# 12-RTL8111H-3.net
KiCad netlist of a schematic drawn in Altium Designer
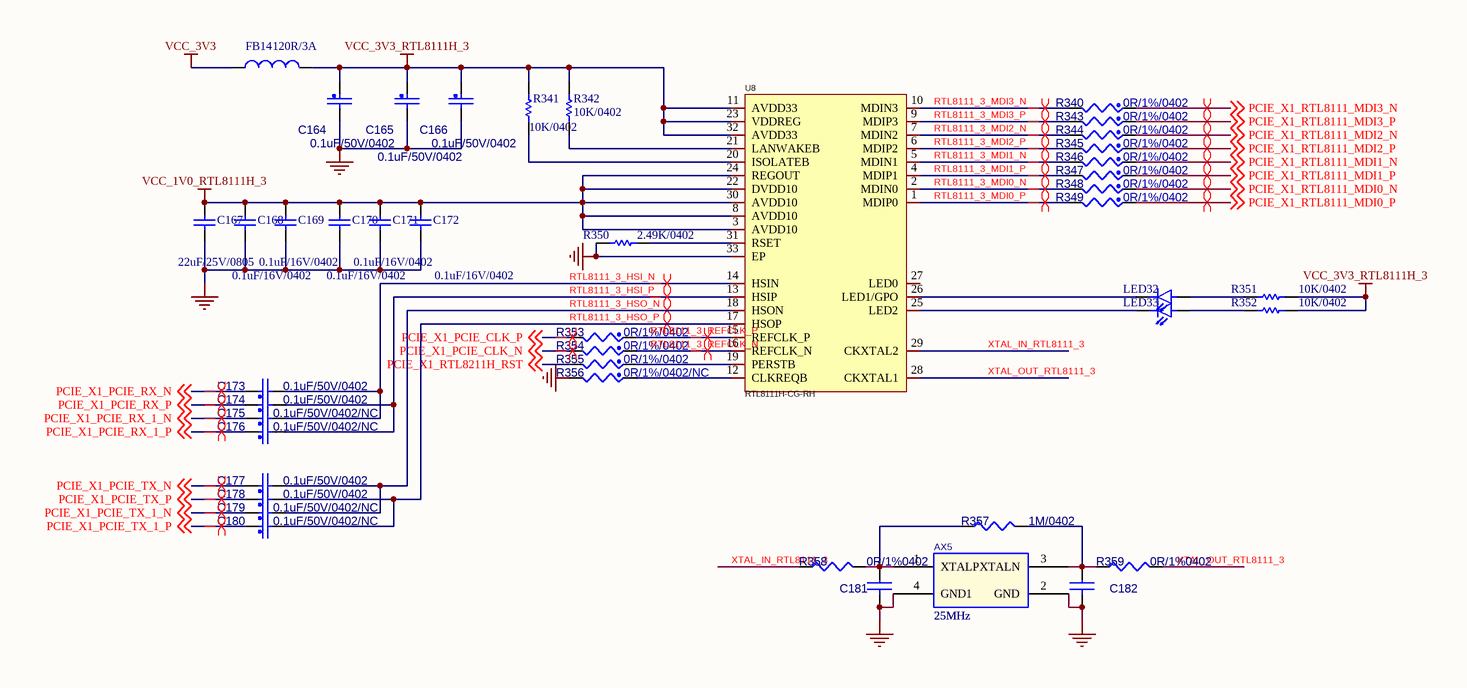
[diagram p0: 12-RTL8111H-3.schdoc]

(export (version "E")
  (design (tool "Eeschema 10.0.6"))
  (components
    (comp (ref "AX5")
      (value "25MHz")
      (footprint "2016")
      (fields (field (name "ALTIUM_VALUE") "25MHz"))
      (libsource (lib "*") (part "XTAL_0"))
    )
    (comp (ref "C164")
      (value "0.1uF/50V/0402")
      (footprint "C0402")
      (description "GCM155R71H104KE02/MURATA")
      (fields (field (name "TOLERANCE") "10%") (field (name "VOLTAGE") "16V"))
      (libsource (lib "*") (part "CAP_NP"))
    )
    (comp (ref "C165")
      (value "0.1uF/50V/0402")
      (footprint "C0402")
      (description "GCM155R71H104KE02/MURATA")
      (fields (field (name "TOLERANCE") "10%") (field (name "VOLTAGE") "16V"))
      (libsource (lib "*") (part "CAP_NP"))
    )
    (comp (ref "C166")
      (value "0.1uF/50V/0402")
      (footprint "C0402")
      (description "GCM155R71H104KE02/MURATA")
      (fields (field (name "TOLERANCE") "10%") (field (name "VOLTAGE") "16V"))
      (libsource (lib "*") (part "CAP_NP"))
    )
    (comp (ref "C167")
      (value "22uF/25V/0805")
      (description "Capacitor")
      (fields (field (name "PUBLISHER") "Altium Limited"))
      (libsource (lib "LIBS") (part "CAP"))
    )
    (comp (ref "C168")
      (value "0.1uF/16V/0402")
      (description "Capacitor")
      (fields (field (name "PUBLISHER") "Altium Limited"))
      (libsource (lib "LIBS") (part "CAP"))
    )
    (comp (ref "C169")
      (value "0.1uF/16V/0402")
      (description "Capacitor")
      (fields (field (name "PUBLISHER") "Altium Limited"))
      (libsource (lib "LIBS") (part "CAP"))
    )
    (comp (ref "C170")
      (value "0.1uF/16V/0402")
      (description "Capacitor")
      (fields (field (name "PUBLISHER") "Altium Limited"))
      (libsource (lib "LIBS") (part "CAP"))
    )
    (comp (ref "C171")
      (value "0.1uF/16V/0402")
      (description "Capacitor")
      (fields (field (name "PUBLISHER") "Altium Limited"))
      (libsource (lib "LIBS") (part "CAP"))
    )
    (comp (ref "C172")
      (value "0.1uF/16V/0402")
      (description "Capacitor")
      (fields (field (name "PUBLISHER") "Altium Limited"))
      (libsource (lib "LIBS") (part "CAP"))
    )
    (comp (ref "C173")
      (value "0.1uF/50V/0402")
      (footprint "C0402")
      (description "GCM155R71H104KE02/MURATA")
      (fields (field (name "TOLERANCE") "10%") (field (name "VOLTAGE") "16V"))
      (libsource (lib "*") (part "CAP_NP"))
    )
    (comp (ref "C174")
      (value "0.1uF/50V/0402")
      (footprint "C0402")
      (description "GCM155R71H104KE02/MURATA")
      (fields (field (name "TOLERANCE") "10%") (field (name "VOLTAGE") "16V"))
      (libsource (lib "*") (part "CAP_NP"))
    )
    (comp (ref "C175")
      (value "0.1uF/50V/0402/NC")
      (footprint "C0402")
      (description "GCM155R71H104KE02/MURATA")
      (fields (field (name "TOLERANCE") "10%") (field (name "VOLTAGE") "16V"))
      (libsource (lib "*") (part "CAP_NP"))
    )
    (comp (ref "C176")
      (value "0.1uF/50V/0402/NC")
      (footprint "C0402")
      (description "GCM155R71H104KE02/MURATA")
      (fields (field (name "TOLERANCE") "10%") (field (name "VOLTAGE") "16V"))
      (libsource (lib "*") (part "CAP_NP"))
    )
    (comp (ref "C177")
      (value "0.1uF/50V/0402")
      (footprint "C0402")
      (description "GCM155R71H104KE02/MURATA")
      (fields (field (name "TOLERANCE") "10%") (field (name "VOLTAGE") "16V"))
      (libsource (lib "*") (part "CAP_NP"))
    )
    (comp (ref "C178")
      (value "0.1uF/50V/0402")
      (footprint "C0402")
      (description "GCM155R71H104KE02/MURATA")
      (fields (field (name "TOLERANCE") "10%") (field (name "VOLTAGE") "16V"))
      (libsource (lib "*") (part "CAP_NP"))
    )
    (comp (ref "C179")
      (value "0.1uF/50V/0402/NC")
      (footprint "C0402")
      (description "GCM155R71H104KE02/MURATA")
      (fields (field (name "TOLERANCE") "10%") (field (name "VOLTAGE") "16V"))
      (libsource (lib "*") (part "CAP_NP"))
    )
    (comp (ref "C180")
      (value "0.1uF/50V/0402/NC")
      (footprint "C0402")
      (description "GCM155R71H104KE02/MURATA")
      (fields (field (name "TOLERANCE") "10%") (field (name "VOLTAGE") "16V"))
      (libsource (lib "*") (part "CAP_NP"))
    )
    (comp (ref "C181") (value "CAP NP_Dup3") (footprint "C0402") (libsource (lib "*") (part "CAP NP_Dup3")))
    (comp (ref "C182") (value "CAP NP_Dup3") (footprint "C0402") (libsource (lib "*") (part "CAP NP_Dup3")))
    (comp (ref "FB14")
      (value "120R/3A")
      (footprint "L0603")
      (description "BLM18KG121TN1D")
      (fields (field (name "PUBLISHER") "Altium Limited"))
      (libsource (lib "LIBS") (part "Inductor"))
    )
    (comp (ref "LED32") (value "LED_GREEN") (footprint "LED0603") (libsource (lib "LIBS") (part "LED")))
    (comp (ref "LED33") (value "LED_GREEN") (footprint "LED0603") (libsource (lib "LIBS") (part "LED")))
    (comp (ref "R340")
      (value "0R/1%/0402")
      (footprint "R0402")
      (description "AC0402FR-070RL/YAGEO")
      (fields (field (name "TOLERANCE") "1%") (field (name "Comment") "RES_Dup2"))
      (libsource (lib "*") (part "RES_Dup2"))
    )
    (comp (ref "R341")
      (value "10K/0402")
      (footprint "R0402")
      (description "Semiconductor Resistor")
      (fields (field (name "PUBLISHER") "Altium Limited"))
      (libsource (lib "LIBS") (part "Res Semi"))
    )
    (comp (ref "R342")
      (value "10K/0402")
      (footprint "R0402")
      (description "Semiconductor Resistor")
      (fields (field (name "PUBLISHER") "Altium Limited"))
      (libsource (lib "LIBS") (part "Res Semi"))
    )
    (comp (ref "R343")
      (value "0R/1%/0402")
      (footprint "R0402")
      (description "AC0402FR-070RL/YAGEO")
      (fields (field (name "TOLERANCE") "1%") (field (name "Comment") "RES_Dup2"))
      (libsource (lib "*") (part "RES_Dup2"))
    )
    (comp (ref "R344")
      (value "0R/1%/0402")
      (footprint "R0402")
      (description "AC0402FR-070RL/YAGEO")
      (fields (field (name "TOLERANCE") "1%") (field (name "Comment") "RES_Dup2"))
      (libsource (lib "*") (part "RES_Dup2"))
    )
    (comp (ref "R345")
      (value "0R/1%/0402")
      (footprint "R0402")
      (description "AC0402FR-070RL/YAGEO")
      (fields (field (name "TOLERANCE") "1%") (field (name "Comment") "RES_Dup2"))
      (libsource (lib "*") (part "RES_Dup2"))
    )
    (comp (ref "R346")
      (value "0R/1%/0402")
      (footprint "R0402")
      (description "AC0402FR-070RL/YAGEO")
      (fields (field (name "TOLERANCE") "1%") (field (name "Comment") "RES_Dup2"))
      (libsource (lib "*") (part "RES_Dup2"))
    )
    (comp (ref "R347")
      (value "0R/1%/0402")
      (footprint "R0402")
      (description "AC0402FR-070RL/YAGEO")
      (fields (field (name "TOLERANCE") "1%") (field (name "Comment") "RES_Dup2"))
      (libsource (lib "*") (part "RES_Dup2"))
    )
    (comp (ref "R348")
      (value "0R/1%/0402")
      (footprint "R0402")
      (description "AC0402FR-070RL/YAGEO")
      (fields (field (name "TOLERANCE") "1%") (field (name "Comment") "RES_Dup2"))
      (libsource (lib "*") (part "RES_Dup2"))
    )
    (comp (ref "R349")
      (value "0R/1%/0402")
      (footprint "R0402")
      (description "AC0402FR-070RL/YAGEO")
      (fields (field (name "TOLERANCE") "1%") (field (name "Comment") "RES_Dup2"))
      (libsource (lib "*") (part "RES_Dup2"))
    )
    (comp (ref "R350")
      (value "2.49K/0402")
      (footprint "R0402")
      (description "Semiconductor Resistor")
      (fields (field (name "PUBLISHER") "Altium Limited"))
      (libsource (lib "LIBS") (part "Res Semi"))
    )
    (comp (ref "R351")
      (value "10K/0402")
      (footprint "R0402")
      (description "Semiconductor Resistor")
      (fields (field (name "PUBLISHER") "Altium Limited"))
      (libsource (lib "LIBS") (part "Res Semi"))
    )
    (comp (ref "R352")
      (value "10K/0402")
      (footprint "R0402")
      (description "Semiconductor Resistor")
      (fields (field (name "PUBLISHER") "Altium Limited"))
      (libsource (lib "LIBS") (part "Res Semi"))
    )
    (comp (ref "R353")
      (value "0R/1%/0402")
      (footprint "R0402")
      (description "AC0402FR-070RL/YAGEO")
      (fields (field (name "TOLERANCE") "1%") (field (name "Comment") "RES_Dup2"))
      (libsource (lib "*") (part "RES_Dup2"))
    )
    (comp (ref "R354")
      (value "0R/1%/0402")
      (footprint "R0402")
      (description "AC0402FR-070RL/YAGEO")
      (fields (field (name "TOLERANCE") "1%") (field (name "Comment") "RES_Dup2"))
      (libsource (lib "*") (part "RES_Dup2"))
    )
    (comp (ref "R355")
      (value "0R/1%/0402")
      (footprint "R0402")
      (description "AC0402FR-070RL/YAGEO")
      (fields (field (name "TOLERANCE") "1%") (field (name "Comment") "RES_Dup2"))
      (libsource (lib "*") (part "RES_Dup2"))
    )
    (comp (ref "R356")
      (value "0R/1%/0402/NC")
      (footprint "R0402")
      (description "AC0402FR-070RL/YAGEO")
      (fields (field (name "TOLERANCE") "1%") (field (name "Comment") "RES_Dup2"))
      (libsource (lib "*") (part "RES_Dup2"))
    )
    (comp (ref "R357")
      (value "1M/0402")
      (footprint "R0402")
      (fields (field (name "Comment") "R_Dup3"))
      (libsource (lib "*") (part "R_Dup3"))
    )
    (comp (ref "R358")
      (value "0R/1%0402")
      (footprint "R0402")
      (fields (field (name "Comment") "R_Dup3"))
      (libsource (lib "*") (part "R_Dup3"))
    )
    (comp (ref "R359")
      (value "0R/1%0402")
      (footprint "R0402")
      (fields (field (name "Comment") "R_Dup3"))
      (libsource (lib "*") (part "R_Dup3"))
    )
    (comp (ref "U8")
      (value "RTL8111H-CG-RH")
      (footprint "RTL8111H-CG-RH")
      (fields (field (name "MANUFACTURER") "REALTEK(瑞昱)") (field (name "MANUFACTURER PART") "RTL8111H-CG"))
      (libsource (lib "17267508141_1726750814") (part "RTL8111H-CG"))
    )
  )
  (nets
    (net (code "1") (name "/RTL8111_3_HSI_N") (class "Default")
      (node (ref "C173") (pin "2") (pinfunction "2_2") (pintype "passive"))
      (node (ref "C175") (pin "2") (pinfunction "2_2") (pintype "passive"))
      (node (ref "U8") (pin "14") (pinfunction "HSIN_14") (pintype "passive"))
    )
    (net (code "2") (name "/RTL8111_3_HSI_P") (class "Default")
      (node (ref "C174") (pin "2") (pinfunction "2_2") (pintype "passive"))
      (node (ref "C176") (pin "2") (pinfunction "2_2") (pintype "passive"))
      (node (ref "U8") (pin "13") (pinfunction "HSIP_13") (pintype "passive"))
    )
    (net (code "3") (name "/RTL8111_3_HSO_N") (class "Default")
      (node (ref "C177") (pin "2") (pinfunction "2_2") (pintype "passive"))
      (node (ref "C179") (pin "2") (pinfunction "2_2") (pintype "passive"))
      (node (ref "U8") (pin "18") (pinfunction "HSON_18") (pintype "passive"))
    )
    (net (code "4") (name "/RTL8111_3_HSO_P") (class "Default")
      (node (ref "C178") (pin "2") (pinfunction "2_2") (pintype "passive"))
      (node (ref "C180") (pin "2") (pinfunction "2_2") (pintype "passive"))
      (node (ref "U8") (pin "17") (pinfunction "HSOP_17") (pintype "passive"))
    )
    (net (code "5") (name "/RTL8111_3_MDI0_N") (class "Default")
      (node (ref "R348") (pin "2") (pinfunction "2_2") (pintype "passive"))
      (node (ref "U8") (pin "2") (pinfunction "MDIN0_2") (pintype "passive"))
    )
    (net (code "6") (name "/RTL8111_3_MDI0_P") (class "Default")
      (node (ref "R349") (pin "2") (pinfunction "2_2") (pintype "passive"))
      (node (ref "U8") (pin "1") (pinfunction "MDIP0_1") (pintype "passive"))
    )
    (net (code "7") (name "/RTL8111_3_MDI1_N") (class "Default")
      (node (ref "R346") (pin "2") (pinfunction "2_2") (pintype "passive"))
      (node (ref "U8") (pin "5") (pinfunction "MDIN1_5") (pintype "passive"))
    )
    (net (code "8") (name "/RTL8111_3_MDI1_P") (class "Default")
      (node (ref "R347") (pin "2") (pinfunction "2_2") (pintype "passive"))
      (node (ref "U8") (pin "4") (pinfunction "MDIP1_4") (pintype "passive"))
    )
    (net (code "9") (name "/RTL8111_3_MDI2_N") (class "Default")
      (node (ref "R344") (pin "2") (pinfunction "2_2") (pintype "passive"))
      (node (ref "U8") (pin "7") (pinfunction "MDIN2_7") (pintype "passive"))
    )
    (net (code "10") (name "/RTL8111_3_MDI2_P") (class "Default")
      (node (ref "R345") (pin "2") (pinfunction "2_2") (pintype "passive"))
      (node (ref "U8") (pin "6") (pinfunction "MDIP2_6") (pintype "passive"))
    )
    (net (code "11") (name "/RTL8111_3_MDI3_N") (class "Default")
      (node (ref "R340") (pin "2") (pinfunction "2_2") (pintype "passive"))
      (node (ref "U8") (pin "10") (pinfunction "MDIN3_10") (pintype "passive"))
    )
    (net (code "12") (name "/RTL8111_3_MDI3_P") (class "Default")
      (node (ref "R343") (pin "2") (pinfunction "2_2") (pintype "passive"))
      (node (ref "U8") (pin "9") (pinfunction "MDIP3_9") (pintype "passive"))
    )
    (net (code "13") (name "/RTL8111_3_REFCLK_N") (class "Default")
      (node (ref "R354") (pin "1") (pinfunction "1_1") (pintype "passive"))
      (node (ref "U8") (pin "16") (pinfunction "REFCLK_N_16") (pintype "passive"))
    )
    (net (code "14") (name "/RTL8111_3_REFCLK_P") (class "Default")
      (node (ref "R353") (pin "1") (pinfunction "1_1") (pintype "passive"))
      (node (ref "U8") (pin "15") (pinfunction "REFCLK_P_15") (pintype "passive"))
    )
    (net (code "15") (name "/XTAL_IN_RTL8111_3") (class "Default")
      (node (ref "R358") (pin "1") (pinfunction "1_1") (pintype "passive"))
      (node (ref "U8") (pin "29") (pinfunction "CKXTAL2_29") (pintype "passive"))
    )
    (net (code "16") (name "/XTAL_OUT_RTL8111_3") (class "Default")
      (node (ref "R359") (pin "2") (pinfunction "2_2") (pintype "passive"))
      (node (ref "U8") (pin "28") (pinfunction "CKXTAL1_28") (pintype "passive"))
    )
    (net (code "17") (name "GND") (class "Default")
      (node (ref "AX5") (pin "2") (pinfunction "GND_2") (pintype "passive"))
      (node (ref "AX5") (pin "4") (pinfunction "GND1_4") (pintype "passive"))
      (node (ref "C164") (pin "2") (pinfunction "2_2") (pintype "passive"))
      (node (ref "C165") (pin "2") (pinfunction "2_2") (pintype "passive"))
      (node (ref "C166") (pin "2") (pinfunction "2_2") (pintype "passive"))
      (node (ref "C167") (pin "1") (pinfunction "1_1") (pintype "passive"))
      (node (ref "C168") (pin "1") (pinfunction "1_1") (pintype "passive"))
      (node (ref "C169") (pin "1") (pinfunction "1_1") (pintype "passive"))
      (node (ref "C170") (pin "1") (pinfunction "1_1") (pintype "passive"))
      (node (ref "C171") (pin "1") (pinfunction "1_1") (pintype "passive"))
      (node (ref "C172") (pin "1") (pinfunction "1_1") (pintype "passive"))
      (node (ref "C181") (pin "2") (pinfunction "2_2") (pintype "passive"))
      (node (ref "C182") (pin "2") (pinfunction "2_2") (pintype "passive"))
      (node (ref "R350") (pin "1") (pinfunction "1_1") (pintype "passive"))
      (node (ref "R356") (pin "2") (pinfunction "2_2") (pintype "passive"))
      (node (ref "U8") (pin "33") (pinfunction "EP_33") (pintype "passive"))
    )
    (net (code "18") (name "Net-(AX5-XTALN)") (class "Default")
      (node (ref "AX5") (pin "3") (pinfunction "XTALN_3") (pintype "passive"))
      (node (ref "C182") (pin "1") (pinfunction "1_1") (pintype "passive"))
      (node (ref "R357") (pin "2") (pinfunction "2_2") (pintype "passive"))
      (node (ref "R359") (pin "1") (pinfunction "1_1") (pintype "passive"))
    )
    (net (code "19") (name "Net-(AX5-XTALP)") (class "Default")
      (node (ref "AX5") (pin "1") (pinfunction "XTALP_1") (pintype "passive"))
      (node (ref "C181") (pin "1") (pinfunction "1_1") (pintype "passive"))
      (node (ref "R357") (pin "1") (pinfunction "1_1") (pintype "passive"))
      (node (ref "R358") (pin "2") (pinfunction "2_2") (pintype "passive"))
    )
    (net (code "20") (name "Net-(LED32-Pad1)") (class "Default")
      (node (ref "LED32") (pin "1") (pinfunction "1_1") (pintype "passive"))
      (node (ref "R351") (pin "2") (pinfunction "2_2") (pintype "passive"))
    )
    (net (code "21") (name "Net-(LED33-Pad1)") (class "Default")
      (node (ref "LED33") (pin "1") (pinfunction "1_1") (pintype "passive"))
      (node (ref "R352") (pin "2") (pinfunction "2_2") (pintype "passive"))
    )
    (net (code "22") (name "Net-(U8-CLKREQB)") (class "Default")
      (node (ref "R356") (pin "1") (pinfunction "1_1") (pintype "passive"))
      (node (ref "U8") (pin "12") (pinfunction "CLKREQB_12") (pintype "passive"))
    )
    (net (code "23") (name "Net-(U8-ISOLATEB)") (class "Default")
      (node (ref "R341") (pin "2") (pinfunction "2_2") (pintype "passive"))
      (node (ref "U8") (pin "20") (pinfunction "ISOLATEB_20") (pintype "passive"))
    )
    (net (code "24") (name "Net-(U8-LANWAKEB)") (class "Default")
      (node (ref "R342") (pin "2") (pinfunction "2_2") (pintype "passive"))
      (node (ref "U8") (pin "21") (pinfunction "LANWAKEB_21") (pintype "passive"))
    )
    (net (code "25") (name "Net-(U8-LED1{slash}GPO)") (class "Default")
      (node (ref "LED32") (pin "2") (pinfunction "2_2") (pintype "passive"))
      (node (ref "U8") (pin "26") (pinfunction "LED1/GPO_26") (pintype "passive"))
    )
    (net (code "26") (name "Net-(U8-LED2)") (class "Default")
      (node (ref "LED33") (pin "2") (pinfunction "2_2") (pintype "passive"))
      (node (ref "U8") (pin "25") (pinfunction "LED2_25") (pintype "passive"))
    )
    (net (code "27") (name "Net-(U8-PERSTB)") (class "Default")
      (node (ref "R355") (pin "1") (pinfunction "1_1") (pintype "passive"))
      (node (ref "U8") (pin "19") (pinfunction "PERSTB_19") (pintype "passive"))
    )
    (net (code "28") (name "Net-(U8-RSET)") (class "Default")
      (node (ref "R350") (pin "2") (pinfunction "2_2") (pintype "passive"))
      (node (ref "U8") (pin "31") (pinfunction "RSET_31") (pintype "passive"))
    )
    (net (code "29") (name "PCIE_X1_PCIE_CLK_N") (class "Default")
      (node (ref "R354") (pin "2") (pinfunction "2_2") (pintype "passive"))
    )
    (net (code "30") (name "PCIE_X1_PCIE_CLK_P") (class "Default")
      (node (ref "R353") (pin "2") (pinfunction "2_2") (pintype "passive"))
    )
    (net (code "31") (name "PCIE_X1_PCIE_RX_1_N") (class "Default")
      (node (ref "C175") (pin "1") (pinfunction "1_1") (pintype "passive"))
    )
    (net (code "32") (name "PCIE_X1_PCIE_RX_1_P") (class "Default")
      (node (ref "C176") (pin "1") (pinfunction "1_1") (pintype "passive"))
    )
    (net (code "33") (name "PCIE_X1_PCIE_RX_N") (class "Default")
      (node (ref "C173") (pin "1") (pinfunction "1_1") (pintype "passive"))
    )
    (net (code "34") (name "PCIE_X1_PCIE_RX_P") (class "Default")
      (node (ref "C174") (pin "1") (pinfunction "1_1") (pintype "passive"))
    )
    (net (code "35") (name "PCIE_X1_PCIE_TX_1_N") (class "Default")
      (node (ref "C179") (pin "1") (pinfunction "1_1") (pintype "passive"))
    )
    (net (code "36") (name "PCIE_X1_PCIE_TX_1_P") (class "Default")
      (node (ref "C180") (pin "1") (pinfunction "1_1") (pintype "passive"))
    )
    (net (code "37") (name "PCIE_X1_PCIE_TX_N") (class "Default")
      (node (ref "C177") (pin "1") (pinfunction "1_1") (pintype "passive"))
    )
    (net (code "38") (name "PCIE_X1_PCIE_TX_P") (class "Default")
      (node (ref "C178") (pin "1") (pinfunction "1_1") (pintype "passive"))
    )
    (net (code "39") (name "PCIE_X1_RTL8111_MDI0_N") (class "Default")
      (node (ref "R348") (pin "1") (pinfunction "1_1") (pintype "passive"))
    )
    (net (code "40") (name "PCIE_X1_RTL8111_MDI0_P") (class "Default")
      (node (ref "R349") (pin "1") (pinfunction "1_1") (pintype "passive"))
    )
    (net (code "41") (name "PCIE_X1_RTL8111_MDI1_N") (class "Default")
      (node (ref "R346") (pin "1") (pinfunction "1_1") (pintype "passive"))
    )
    (net (code "42") (name "PCIE_X1_RTL8111_MDI1_P") (class "Default")
      (node (ref "R347") (pin "1") (pinfunction "1_1") (pintype "passive"))
    )
    (net (code "43") (name "PCIE_X1_RTL8111_MDI2_N") (class "Default")
      (node (ref "R344") (pin "1") (pinfunction "1_1") (pintype "passive"))
    )
    (net (code "44") (name "PCIE_X1_RTL8111_MDI2_P") (class "Default")
      (node (ref "R345") (pin "1") (pinfunction "1_1") (pintype "passive"))
    )
    (net (code "45") (name "PCIE_X1_RTL8111_MDI3_N") (class "Default")
      (node (ref "R340") (pin "1") (pinfunction "1_1") (pintype "passive"))
    )
    (net (code "46") (name "PCIE_X1_RTL8111_MDI3_P") (class "Default")
      (node (ref "R343") (pin "1") (pinfunction "1_1") (pintype "passive"))
    )
    (net (code "47") (name "PCIE_X1_RTL8211H_RST") (class "Default")
      (node (ref "R355") (pin "2") (pinfunction "2_2") (pintype "passive"))
    )
    (net (code "48") (name "VCC_1V0_RTL8111H_3") (class "Default")
      (node (ref "C167") (pin "2") (pinfunction "2_2") (pintype "passive"))
      (node (ref "C168") (pin "2") (pinfunction "2_2") (pintype "passive"))
      (node (ref "C169") (pin "2") (pinfunction "2_2") (pintype "passive"))
      (node (ref "C170") (pin "2") (pinfunction "2_2") (pintype "passive"))
      (node (ref "C171") (pin "2") (pinfunction "2_2") (pintype "passive"))
      (node (ref "C172") (pin "2") (pinfunction "2_2") (pintype "passive"))
      (node (ref "U8") (pin "22") (pinfunction "DVDD10_22") (pintype "passive"))
      (node (ref "U8") (pin "24") (pinfunction "REGOUT_24") (pintype "passive"))
      (node (ref "U8") (pin "3") (pinfunction "AVDD10_3") (pintype "passive"))
      (node (ref "U8") (pin "30") (pinfunction "AVDD10_30") (pintype "passive"))
      (node (ref "U8") (pin "8") (pinfunction "AVDD10_8") (pintype "passive"))
    )
    (net (code "49") (name "VCC_3V3") (class "Default")
      (node (ref "FB14") (pin "1") (pinfunction "1_1") (pintype "passive"))
    )
    (net (code "50") (name "VCC_3V3_RTL8111H_3") (class "Default")
      (node (ref "C164") (pin "1") (pinfunction "1_1") (pintype "passive"))
      (node (ref "C165") (pin "1") (pinfunction "1_1") (pintype "passive"))
      (node (ref "C166") (pin "1") (pinfunction "1_1") (pintype "passive"))
      (node (ref "FB14") (pin "2") (pinfunction "2_2") (pintype "passive"))
      (node (ref "R341") (pin "1") (pinfunction "1_1") (pintype "passive"))
      (node (ref "R342") (pin "1") (pinfunction "1_1") (pintype "passive"))
      (node (ref "R351") (pin "1") (pinfunction "1_1") (pintype "passive"))
      (node (ref "R352") (pin "1") (pinfunction "1_1") (pintype "passive"))
      (node (ref "U8") (pin "11") (pinfunction "AVDD33_11") (pintype "passive"))
      (node (ref "U8") (pin "23") (pinfunction "VDDREG_23") (pintype "passive"))
      (node (ref "U8") (pin "32") (pinfunction "AVDD33_32") (pintype "passive"))
    )
    (net (code "51") (name "unconnected-(U8-LED0-Pad27)") (class "Default")
      (node (ref "U8") (pin "27") (pinfunction "LED0_27") (pintype "passive"))
    )
  )
)
